# cherryKeyShield.net
KiCad netlist of a schematic drawn in EAGLE
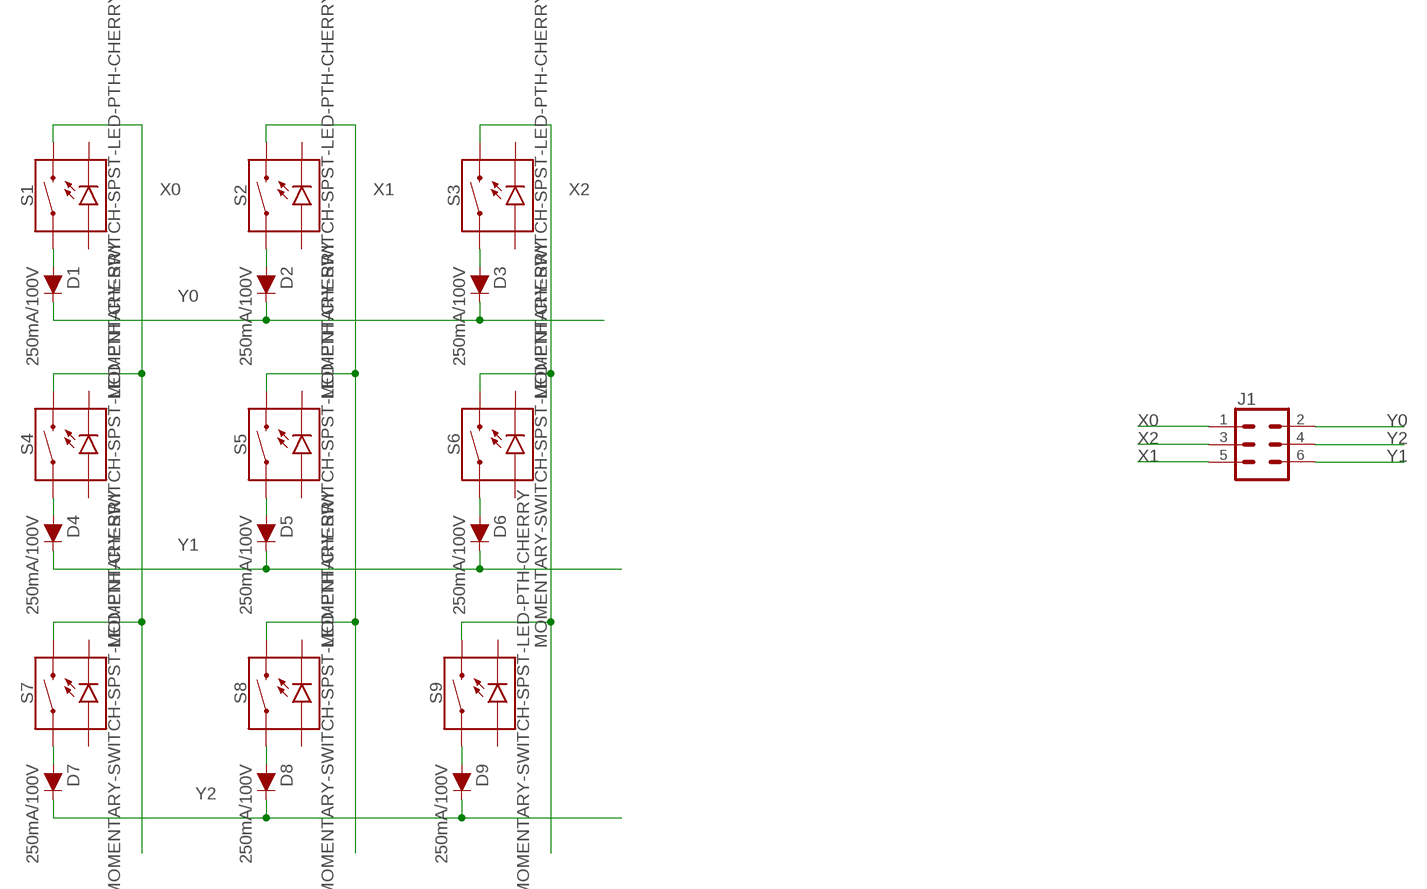
[diagram p0: schematic, sheet 1]

(export (version "E")
  (design (tool "Eeschema 10.0.6"))
  (components
    (comp (ref "D1")
      (value "250mA/100V")
      (footprint "eagle-import:SOD-323")
      (libsource (lib "eagle-import") (part "DIODE-BAS16J"))
    )
    (comp (ref "D2")
      (value "250mA/100V")
      (footprint "eagle-import:SOD-323")
      (libsource (lib "eagle-import") (part "DIODE-BAS16J"))
    )
    (comp (ref "D3")
      (value "250mA/100V")
      (footprint "eagle-import:SOD-323")
      (libsource (lib "eagle-import") (part "DIODE-BAS16J"))
    )
    (comp (ref "D4")
      (value "250mA/100V")
      (footprint "eagle-import:SOD-323")
      (libsource (lib "eagle-import") (part "DIODE-BAS16J"))
    )
    (comp (ref "D5")
      (value "250mA/100V")
      (footprint "eagle-import:SOD-323")
      (libsource (lib "eagle-import") (part "DIODE-BAS16J"))
    )
    (comp (ref "D6")
      (value "250mA/100V")
      (footprint "eagle-import:SOD-323")
      (libsource (lib "eagle-import") (part "DIODE-BAS16J"))
    )
    (comp (ref "D7")
      (value "250mA/100V")
      (footprint "eagle-import:SOD-323")
      (libsource (lib "eagle-import") (part "DIODE-BAS16J"))
    )
    (comp (ref "D8")
      (value "250mA/100V")
      (footprint "eagle-import:SOD-323")
      (libsource (lib "eagle-import") (part "DIODE-BAS16J"))
    )
    (comp (ref "D9")
      (value "250mA/100V")
      (footprint "eagle-import:SOD-323")
      (libsource (lib "eagle-import") (part "DIODE-BAS16J"))
    )
    (comp (ref "J1")
      (value "CONN_03X22X3_SILK_MALE_PTH")
      (footprint "eagle-import:2X3")
      (libsource (lib "eagle-import") (part "CONN_03X22X3_SILK_MALE_PTH"))
    )
    (comp (ref "S1")
      (value "MOMENTARY-SWITCH-SPST-LED-PTH-CHERRY")
      (footprint "eagle-import:CHERRY-MX-LED")
      (libsource (lib "eagle-import") (part "MOMENTARY-SWITCH-SPST-LED-PTH-CHERRY"))
    )
    (comp (ref "S2")
      (value "MOMENTARY-SWITCH-SPST-LED-PTH-CHERRY")
      (footprint "eagle-import:CHERRY-MX-LED")
      (libsource (lib "eagle-import") (part "MOMENTARY-SWITCH-SPST-LED-PTH-CHERRY"))
    )
    (comp (ref "S3")
      (value "MOMENTARY-SWITCH-SPST-LED-PTH-CHERRY")
      (footprint "eagle-import:CHERRY-MX-LED")
      (libsource (lib "eagle-import") (part "MOMENTARY-SWITCH-SPST-LED-PTH-CHERRY"))
    )
    (comp (ref "S4")
      (value "MOMENTARY-SWITCH-SPST-LED-PTH-CHERRY")
      (footprint "eagle-import:CHERRY-MX-LED")
      (libsource (lib "eagle-import") (part "MOMENTARY-SWITCH-SPST-LED-PTH-CHERRY"))
    )
    (comp (ref "S5")
      (value "MOMENTARY-SWITCH-SPST-LED-PTH-CHERRY")
      (footprint "eagle-import:CHERRY-MX-LED")
      (libsource (lib "eagle-import") (part "MOMENTARY-SWITCH-SPST-LED-PTH-CHERRY"))
    )
    (comp (ref "S6")
      (value "MOMENTARY-SWITCH-SPST-LED-PTH-CHERRY")
      (footprint "eagle-import:CHERRY-MX-LED")
      (libsource (lib "eagle-import") (part "MOMENTARY-SWITCH-SPST-LED-PTH-CHERRY"))
    )
    (comp (ref "S7")
      (value "MOMENTARY-SWITCH-SPST-LED-PTH-CHERRY")
      (footprint "eagle-import:CHERRY-MX-LED")
      (libsource (lib "eagle-import") (part "MOMENTARY-SWITCH-SPST-LED-PTH-CHERRY"))
    )
    (comp (ref "S8")
      (value "MOMENTARY-SWITCH-SPST-LED-PTH-CHERRY")
      (footprint "eagle-import:CHERRY-MX-LED")
      (libsource (lib "eagle-import") (part "MOMENTARY-SWITCH-SPST-LED-PTH-CHERRY"))
    )
    (comp (ref "S9")
      (value "MOMENTARY-SWITCH-SPST-LED-PTH-CHERRY")
      (footprint "eagle-import:CHERRY-MX-LED")
      (libsource (lib "eagle-import") (part "MOMENTARY-SWITCH-SPST-LED-PTH-CHERRY"))
    )
  )
  (nets
    (net (code "1") (name "/X0") (class "Default")
      (node (ref "J1") (pin "1") (pinfunction "1_1") (pintype "bidirectional"))
      (node (ref "S1") (pin "S2") (pinfunction "2_S2") (pintype "passive"))
      (node (ref "S4") (pin "S2") (pinfunction "2_S2") (pintype "passive"))
      (node (ref "S7") (pin "S2") (pinfunction "2_S2") (pintype "passive"))
    )
    (net (code "2") (name "/X1") (class "Default")
      (node (ref "J1") (pin "5") (pinfunction "5_5") (pintype "bidirectional"))
      (node (ref "S2") (pin "S2") (pinfunction "2_S2") (pintype "passive"))
      (node (ref "S5") (pin "S2") (pinfunction "2_S2") (pintype "passive"))
      (node (ref "S8") (pin "S2") (pinfunction "2_S2") (pintype "passive"))
    )
    (net (code "3") (name "/X2") (class "Default")
      (node (ref "J1") (pin "3") (pinfunction "3_3") (pintype "bidirectional"))
      (node (ref "S3") (pin "S2") (pinfunction "2_S2") (pintype "passive"))
      (node (ref "S6") (pin "S2") (pinfunction "2_S2") (pintype "passive"))
      (node (ref "S9") (pin "S2") (pinfunction "2_S2") (pintype "passive"))
    )
    (net (code "4") (name "/Y0") (class "Default")
      (node (ref "D1") (pin "C") (pinfunction "C_C") (pintype "passive"))
      (node (ref "D2") (pin "C") (pinfunction "C_C") (pintype "passive"))
      (node (ref "D3") (pin "C") (pinfunction "C_C") (pintype "passive"))
      (node (ref "J1") (pin "2") (pinfunction "2_2") (pintype "bidirectional"))
    )
    (net (code "5") (name "/Y1") (class "Default")
      (node (ref "D4") (pin "C") (pinfunction "C_C") (pintype "passive"))
      (node (ref "D5") (pin "C") (pinfunction "C_C") (pintype "passive"))
      (node (ref "D6") (pin "C") (pinfunction "C_C") (pintype "passive"))
      (node (ref "J1") (pin "6") (pinfunction "6_6") (pintype "bidirectional"))
    )
    (net (code "6") (name "/Y2") (class "Default")
      (node (ref "D7") (pin "C") (pinfunction "C_C") (pintype "passive"))
      (node (ref "D8") (pin "C") (pinfunction "C_C") (pintype "passive"))
      (node (ref "D9") (pin "C") (pinfunction "C_C") (pintype "passive"))
      (node (ref "J1") (pin "4") (pinfunction "4_4") (pintype "bidirectional"))
    )
    (net (code "7") (name "Net-(S1-1)") (class "Default")
      (node (ref "D1") (pin "A") (pinfunction "A_A") (pintype "passive"))
      (node (ref "S1") (pin "S1") (pinfunction "1_S1") (pintype "passive"))
    )
    (net (code "8") (name "Net-(S2-1)") (class "Default")
      (node (ref "D2") (pin "A") (pinfunction "A_A") (pintype "passive"))
      (node (ref "S2") (pin "S1") (pinfunction "1_S1") (pintype "passive"))
    )
    (net (code "9") (name "Net-(S3-1)") (class "Default")
      (node (ref "D3") (pin "A") (pinfunction "A_A") (pintype "passive"))
      (node (ref "S3") (pin "S1") (pinfunction "1_S1") (pintype "passive"))
    )
    (net (code "10") (name "Net-(S4-1)") (class "Default")
      (node (ref "D4") (pin "A") (pinfunction "A_A") (pintype "passive"))
      (node (ref "S4") (pin "S1") (pinfunction "1_S1") (pintype "passive"))
    )
    (net (code "11") (name "Net-(S5-1)") (class "Default")
      (node (ref "D5") (pin "A") (pinfunction "A_A") (pintype "passive"))
      (node (ref "S5") (pin "S1") (pinfunction "1_S1") (pintype "passive"))
    )
    (net (code "12") (name "Net-(S6-1)") (class "Default")
      (node (ref "D6") (pin "A") (pinfunction "A_A") (pintype "passive"))
      (node (ref "S6") (pin "S1") (pinfunction "1_S1") (pintype "passive"))
    )
    (net (code "13") (name "Net-(S7-1)") (class "Default")
      (node (ref "D7") (pin "A") (pinfunction "A_A") (pintype "passive"))
      (node (ref "S7") (pin "S1") (pinfunction "1_S1") (pintype "passive"))
    )
    (net (code "14") (name "Net-(S8-1)") (class "Default")
      (node (ref "D8") (pin "A") (pinfunction "A_A") (pintype "passive"))
      (node (ref "S8") (pin "S1") (pinfunction "1_S1") (pintype "passive"))
    )
    (net (code "15") (name "Net-(S9-1)") (class "Default")
      (node (ref "D9") (pin "A") (pinfunction "A_A") (pintype "passive"))
      (node (ref "S9") (pin "S1") (pinfunction "1_S1") (pintype "passive"))
    )
    (net (code "16") (name "unconnected-(S1-C-PadK)") (class "Default")
      (node (ref "S1") (pin "K") (pinfunction "C_K") (pintype "passive"))
    )
    (net (code "17") (name "unconnected-(S1-PadA)") (class "Default")
      (node (ref "S1") (pin "A") (pinfunction "A_A") (pintype "passive"))
    )
    (net (code "18") (name "unconnected-(S2-C-PadK)") (class "Default")
      (node (ref "S2") (pin "K") (pinfunction "C_K") (pintype "passive"))
    )
    (net (code "19") (name "unconnected-(S2-PadA)") (class "Default")
      (node (ref "S2") (pin "A") (pinfunction "A_A") (pintype "passive"))
    )
    (net (code "20") (name "unconnected-(S3-C-PadK)") (class "Default")
      (node (ref "S3") (pin "K") (pinfunction "C_K") (pintype "passive"))
    )
    (net (code "21") (name "unconnected-(S3-PadA)") (class "Default")
      (node (ref "S3") (pin "A") (pinfunction "A_A") (pintype "passive"))
    )
    (net (code "22") (name "unconnected-(S4-C-PadK)") (class "Default")
      (node (ref "S4") (pin "K") (pinfunction "C_K") (pintype "passive"))
    )
    (net (code "23") (name "unconnected-(S4-PadA)") (class "Default")
      (node (ref "S4") (pin "A") (pinfunction "A_A") (pintype "passive"))
    )
    (net (code "24") (name "unconnected-(S5-C-PadK)") (class "Default")
      (node (ref "S5") (pin "K") (pinfunction "C_K") (pintype "passive"))
    )
    (net (code "25") (name "unconnected-(S5-PadA)") (class "Default")
      (node (ref "S5") (pin "A") (pinfunction "A_A") (pintype "passive"))
    )
    (net (code "26") (name "unconnected-(S6-C-PadK)") (class "Default")
      (node (ref "S6") (pin "K") (pinfunction "C_K") (pintype "passive"))
    )
    (net (code "27") (name "unconnected-(S6-PadA)") (class "Default")
      (node (ref "S6") (pin "A") (pinfunction "A_A") (pintype "passive"))
    )
    (net (code "28") (name "unconnected-(S7-C-PadK)") (class "Default")
      (node (ref "S7") (pin "K") (pinfunction "C_K") (pintype "passive"))
    )
    (net (code "29") (name "unconnected-(S7-PadA)") (class "Default")
      (node (ref "S7") (pin "A") (pinfunction "A_A") (pintype "passive"))
    )
    (net (code "30") (name "unconnected-(S8-C-PadK)") (class "Default")
      (node (ref "S8") (pin "K") (pinfunction "C_K") (pintype "passive"))
    )
    (net (code "31") (name "unconnected-(S8-PadA)") (class "Default")
      (node (ref "S8") (pin "A") (pinfunction "A_A") (pintype "passive"))
    )
    (net (code "32") (name "unconnected-(S9-C-PadK)") (class "Default")
      (node (ref "S9") (pin "K") (pinfunction "C_K") (pintype "passive"))
    )
    (net (code "33") (name "unconnected-(S9-PadA)") (class "Default")
      (node (ref "S9") (pin "A") (pinfunction "A_A") (pintype "passive"))
    )
  )
)
